# 3_Motor.net
KiCad netlist of a schematic drawn in Altium Designer
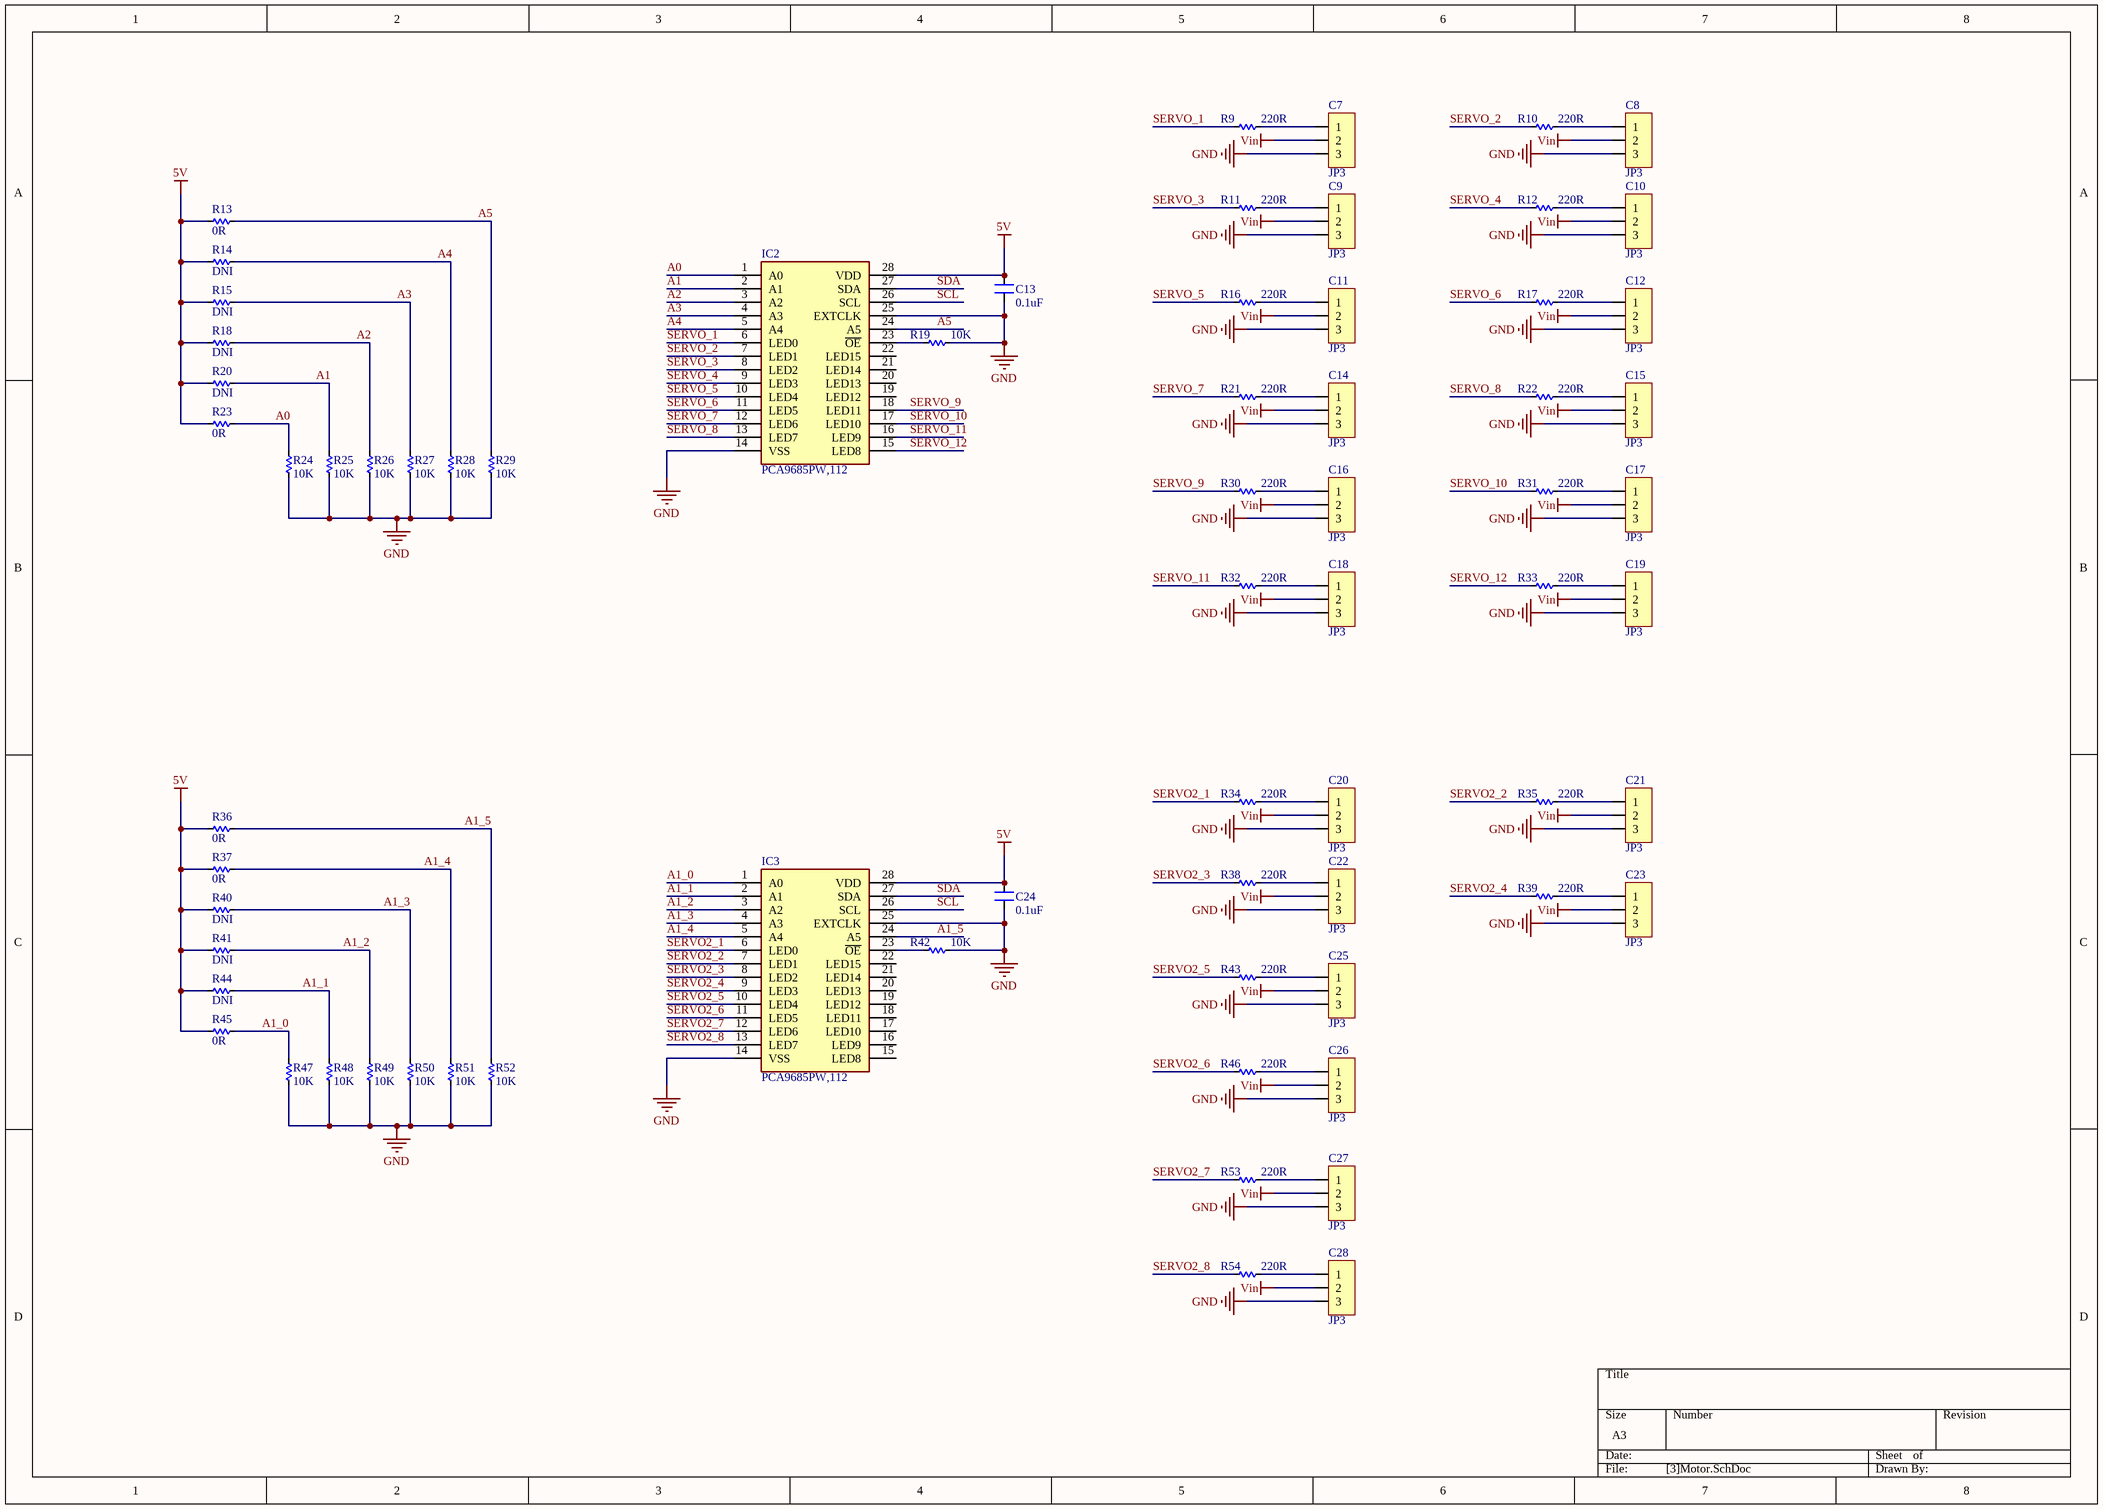
[diagram p0: [3]Motor.SchDoc]

(export (version "E")
  (design (tool "Eeschema 10.0.6"))
  (components
    (comp (ref "C7")
      (value "JP3")
      (footprint "JP3-D1T")
      (description "WR-PHD 2.54 mm Angled Socket Header")
      (fields
        (field (name "MANUFACTURER") "Würth Elektronik eiSos GmbH")
        (field (name "PARTNO") "613003143121")
        (field (name "CREATED BY") "Karrer Zheng")
      )
      (libsource (lib "LIBRARY") (part "JP3"))
    )
    (comp (ref "C8")
      (value "JP3")
      (footprint "JP3-D1T")
      (description "WR-PHD 2.54 mm Angled Socket Header")
      (fields
        (field (name "MANUFACTURER") "Würth Elektronik eiSos GmbH")
        (field (name "PARTNO") "613003143121")
        (field (name "CREATED BY") "Karrer Zheng")
      )
      (libsource (lib "LIBRARY") (part "JP3"))
    )
    (comp (ref "C9")
      (value "JP3")
      (footprint "JP3-D1T")
      (description "WR-PHD 2.54 mm Angled Socket Header")
      (fields
        (field (name "MANUFACTURER") "Würth Elektronik eiSos GmbH")
        (field (name "PARTNO") "613003143121")
        (field (name "CREATED BY") "Karrer Zheng")
      )
      (libsource (lib "LIBRARY") (part "JP3"))
    )
    (comp (ref "C10")
      (value "JP3")
      (footprint "JP3-D1T")
      (description "WR-PHD 2.54 mm Angled Socket Header")
      (fields
        (field (name "MANUFACTURER") "Würth Elektronik eiSos GmbH")
        (field (name "PARTNO") "613003143121")
        (field (name "CREATED BY") "Karrer Zheng")
      )
      (libsource (lib "LIBRARY") (part "JP3"))
    )
    (comp (ref "C11")
      (value "JP3")
      (footprint "JP3-D1T")
      (description "WR-PHD 2.54 mm Angled Socket Header")
      (fields
        (field (name "MANUFACTURER") "Würth Elektronik eiSos GmbH")
        (field (name "PARTNO") "613003143121")
        (field (name "CREATED BY") "Karrer Zheng")
      )
      (libsource (lib "LIBRARY") (part "JP3"))
    )
    (comp (ref "C12")
      (value "JP3")
      (footprint "JP3-D1T")
      (description "WR-PHD 2.54 mm Angled Socket Header")
      (fields
        (field (name "MANUFACTURER") "Würth Elektronik eiSos GmbH")
        (field (name "PARTNO") "613003143121")
        (field (name "CREATED BY") "Karrer Zheng")
      )
      (libsource (lib "LIBRARY") (part "JP3"))
    )
    (comp (ref "C13")
      (value "0.1uF")
      (footprint "CN-SMD-0603")
      (description "Tu gom")
      (libsource (lib "LIBTanCN") (part "CN"))
    )
    (comp (ref "C14")
      (value "JP3")
      (footprint "JP3-D1T")
      (description "WR-PHD 2.54 mm Angled Socket Header")
      (fields
        (field (name "MANUFACTURER") "Würth Elektronik eiSos GmbH")
        (field (name "PARTNO") "613003143121")
        (field (name "CREATED BY") "Karrer Zheng")
      )
      (libsource (lib "LIBRARY") (part "JP3"))
    )
    (comp (ref "C15")
      (value "JP3")
      (footprint "JP3-D1T")
      (description "WR-PHD 2.54 mm Angled Socket Header")
      (fields
        (field (name "MANUFACTURER") "Würth Elektronik eiSos GmbH")
        (field (name "PARTNO") "613003143121")
        (field (name "CREATED BY") "Karrer Zheng")
      )
      (libsource (lib "LIBRARY") (part "JP3"))
    )
    (comp (ref "C16")
      (value "JP3")
      (footprint "JP3-D1T")
      (description "WR-PHD 2.54 mm Angled Socket Header")
      (fields
        (field (name "MANUFACTURER") "Würth Elektronik eiSos GmbH")
        (field (name "PARTNO") "613003143121")
        (field (name "CREATED BY") "Karrer Zheng")
      )
      (libsource (lib "LIBRARY") (part "JP3"))
    )
    (comp (ref "C17")
      (value "JP3")
      (footprint "JP3-D1T")
      (description "WR-PHD 2.54 mm Angled Socket Header")
      (fields
        (field (name "MANUFACTURER") "Würth Elektronik eiSos GmbH")
        (field (name "PARTNO") "613003143121")
        (field (name "CREATED BY") "Karrer Zheng")
      )
      (libsource (lib "LIBRARY") (part "JP3"))
    )
    (comp (ref "C18")
      (value "JP3")
      (footprint "JP3-D1T")
      (description "WR-PHD 2.54 mm Angled Socket Header")
      (fields
        (field (name "MANUFACTURER") "Würth Elektronik eiSos GmbH")
        (field (name "PARTNO") "613003143121")
        (field (name "CREATED BY") "Karrer Zheng")
      )
      (libsource (lib "LIBRARY") (part "JP3"))
    )
    (comp (ref "C19")
      (value "JP3")
      (footprint "JP3-D1T")
      (description "WR-PHD 2.54 mm Angled Socket Header")
      (fields
        (field (name "MANUFACTURER") "Würth Elektronik eiSos GmbH")
        (field (name "PARTNO") "613003143121")
        (field (name "CREATED BY") "Karrer Zheng")
      )
      (libsource (lib "LIBRARY") (part "JP3"))
    )
    (comp (ref "C20")
      (value "JP3")
      (footprint "JP3-D1T")
      (description "WR-PHD 2.54 mm Angled Socket Header")
      (fields
        (field (name "MANUFACTURER") "Würth Elektronik eiSos GmbH")
        (field (name "PARTNO") "613003143121")
        (field (name "CREATED BY") "Karrer Zheng")
      )
      (libsource (lib "LIBRARY") (part "JP3"))
    )
    (comp (ref "C21")
      (value "JP3")
      (footprint "JP3-D1T")
      (description "WR-PHD 2.54 mm Angled Socket Header")
      (fields
        (field (name "MANUFACTURER") "Würth Elektronik eiSos GmbH")
        (field (name "PARTNO") "613003143121")
        (field (name "CREATED BY") "Karrer Zheng")
      )
      (libsource (lib "LIBRARY") (part "JP3"))
    )
    (comp (ref "C22")
      (value "JP3")
      (footprint "JP3-D1T")
      (description "WR-PHD 2.54 mm Angled Socket Header")
      (fields
        (field (name "MANUFACTURER") "Würth Elektronik eiSos GmbH")
        (field (name "PARTNO") "613003143121")
        (field (name "CREATED BY") "Karrer Zheng")
      )
      (libsource (lib "LIBRARY") (part "JP3"))
    )
    (comp (ref "C23")
      (value "JP3")
      (footprint "JP3-D1T")
      (description "WR-PHD 2.54 mm Angled Socket Header")
      (fields
        (field (name "MANUFACTURER") "Würth Elektronik eiSos GmbH")
        (field (name "PARTNO") "613003143121")
        (field (name "CREATED BY") "Karrer Zheng")
      )
      (libsource (lib "LIBRARY") (part "JP3"))
    )
    (comp (ref "C24")
      (value "0.1uF")
      (footprint "CN-SMD-0603")
      (description "Tu gom")
      (libsource (lib "LIBTanCN") (part "CN"))
    )
    (comp (ref "C25")
      (value "JP3")
      (footprint "JP3-D1T")
      (description "WR-PHD 2.54 mm Angled Socket Header")
      (fields
        (field (name "MANUFACTURER") "Würth Elektronik eiSos GmbH")
        (field (name "PARTNO") "613003143121")
        (field (name "CREATED BY") "Karrer Zheng")
      )
      (libsource (lib "LIBRARY") (part "JP3"))
    )
    (comp (ref "C26")
      (value "JP3")
      (footprint "JP3-D1T")
      (description "WR-PHD 2.54 mm Angled Socket Header")
      (fields
        (field (name "MANUFACTURER") "Würth Elektronik eiSos GmbH")
        (field (name "PARTNO") "613003143121")
        (field (name "CREATED BY") "Karrer Zheng")
      )
      (libsource (lib "LIBRARY") (part "JP3"))
    )
    (comp (ref "C27")
      (value "JP3")
      (footprint "JP3-D1T")
      (description "WR-PHD 2.54 mm Angled Socket Header")
      (fields
        (field (name "MANUFACTURER") "Würth Elektronik eiSos GmbH")
        (field (name "PARTNO") "613003143121")
        (field (name "CREATED BY") "Karrer Zheng")
      )
      (libsource (lib "LIBRARY") (part "JP3"))
    )
    (comp (ref "C28")
      (value "JP3")
      (footprint "JP3-D1T")
      (description "WR-PHD 2.54 mm Angled Socket Header")
      (fields
        (field (name "MANUFACTURER") "Würth Elektronik eiSos GmbH")
        (field (name "PARTNO") "613003143121")
        (field (name "CREATED BY") "Karrer Zheng")
      )
      (libsource (lib "LIBRARY") (part "JP3"))
    )
    (comp (ref "IC2")
      (value "PCA9685PW,112")
      (footprint "SamacSys:SOP65P640X110-28N")
      (description "Integrated Circuit")
      (fields (field (name "MOUSER PART NUMBER") "771-PCA9685PW,112"))
      (libsource (lib "*") (part "PCA9685PW,112"))
    )
    (comp (ref "IC3")
      (value "PCA9685PW,112")
      (footprint "SamacSys:SOP65P640X110-28N")
      (description "Integrated Circuit")
      (fields (field (name "MOUSER PART NUMBER") "771-PCA9685PW,112"))
      (libsource (lib "*") (part "PCA9685PW,112"))
    )
    (comp (ref "R9")
      (value "220R")
      (footprint "RES-SMD-0603")
      (description "Resistor")
      (fields
        (field (name "MANUFACTURER") "Generic Components")
        (field (name "PUBLISHER") "Altium Hobart Technology Centre")
      )
      (libsource (lib "LIBRARY") (part "Res-SMD"))
    )
    (comp (ref "R10")
      (value "220R")
      (footprint "RES-SMD-0603")
      (description "Resistor")
      (fields
        (field (name "MANUFACTURER") "Generic Components")
        (field (name "PUBLISHER") "Altium Hobart Technology Centre")
      )
      (libsource (lib "LIBRARY") (part "Res-SMD"))
    )
    (comp (ref "R11")
      (value "220R")
      (footprint "RES-SMD-0603")
      (description "Resistor")
      (fields
        (field (name "MANUFACTURER") "Generic Components")
        (field (name "PUBLISHER") "Altium Hobart Technology Centre")
      )
      (libsource (lib "LIBRARY") (part "Res-SMD"))
    )
    (comp (ref "R12")
      (value "220R")
      (footprint "RES-SMD-0603")
      (description "Resistor")
      (fields
        (field (name "MANUFACTURER") "Generic Components")
        (field (name "PUBLISHER") "Altium Hobart Technology Centre")
      )
      (libsource (lib "LIBRARY") (part "Res-SMD"))
    )
    (comp (ref "R13")
      (value "0R")
      (footprint "RES-SMD-0603")
      (description "Resistor")
      (fields
        (field (name "MANUFACTURER") "Generic Components")
        (field (name "PUBLISHER") "Altium Hobart Technology Centre")
      )
      (libsource (lib "LIBRARY") (part "Res-SMD"))
    )
    (comp (ref "R14")
      (value "DNI")
      (footprint "RES-SMD-0603")
      (description "Resistor")
      (fields
        (field (name "MANUFACTURER") "Generic Components")
        (field (name "PUBLISHER") "Altium Hobart Technology Centre")
      )
      (libsource (lib "LIBRARY") (part "Res-SMD"))
    )
    (comp (ref "R15")
      (value "DNI")
      (footprint "RES-SMD-0603")
      (description "Resistor")
      (fields
        (field (name "MANUFACTURER") "Generic Components")
        (field (name "PUBLISHER") "Altium Hobart Technology Centre")
      )
      (libsource (lib "LIBRARY") (part "Res-SMD"))
    )
    (comp (ref "R16")
      (value "220R")
      (footprint "RES-SMD-0603")
      (description "Resistor")
      (fields
        (field (name "MANUFACTURER") "Generic Components")
        (field (name "PUBLISHER") "Altium Hobart Technology Centre")
      )
      (libsource (lib "LIBRARY") (part "Res-SMD"))
    )
    (comp (ref "R17")
      (value "220R")
      (footprint "RES-SMD-0603")
      (description "Resistor")
      (fields
        (field (name "MANUFACTURER") "Generic Components")
        (field (name "PUBLISHER") "Altium Hobart Technology Centre")
      )
      (libsource (lib "LIBRARY") (part "Res-SMD"))
    )
    (comp (ref "R18")
      (value "DNI")
      (footprint "RES-SMD-0603")
      (description "Resistor")
      (fields
        (field (name "MANUFACTURER") "Generic Components")
        (field (name "PUBLISHER") "Altium Hobart Technology Centre")
      )
      (libsource (lib "LIBRARY") (part "Res-SMD"))
    )
    (comp (ref "R19")
      (value "10K")
      (footprint "RES-SMD-0603")
      (description "Resistor")
      (fields
        (field (name "MANUFACTURER") "Generic Components")
        (field (name "PUBLISHER") "Altium Hobart Technology Centre")
      )
      (libsource (lib "LIBRARY") (part "Res-SMD"))
    )
    (comp (ref "R20")
      (value "DNI")
      (footprint "RES-SMD-0603")
      (description "Resistor")
      (fields
        (field (name "MANUFACTURER") "Generic Components")
        (field (name "PUBLISHER") "Altium Hobart Technology Centre")
      )
      (libsource (lib "LIBRARY") (part "Res-SMD"))
    )
    (comp (ref "R21")
      (value "220R")
      (footprint "RES-SMD-0603")
      (description "Resistor")
      (fields
        (field (name "MANUFACTURER") "Generic Components")
        (field (name "PUBLISHER") "Altium Hobart Technology Centre")
      )
      (libsource (lib "LIBRARY") (part "Res-SMD"))
    )
    (comp (ref "R22")
      (value "220R")
      (footprint "RES-SMD-0603")
      (description "Resistor")
      (fields
        (field (name "MANUFACTURER") "Generic Components")
        (field (name "PUBLISHER") "Altium Hobart Technology Centre")
      )
      (libsource (lib "LIBRARY") (part "Res-SMD"))
    )
    (comp (ref "R23")
      (value "0R")
      (footprint "RES-SMD-0603")
      (description "Resistor")
      (fields
        (field (name "MANUFACTURER") "Generic Components")
        (field (name "PUBLISHER") "Altium Hobart Technology Centre")
      )
      (libsource (lib "LIBRARY") (part "Res-SMD"))
    )
    (comp (ref "R24")
      (value "10K")
      (footprint "RES-SMD-0603")
      (description "Resistor")
      (fields
        (field (name "MANUFACTURER") "Generic Components")
        (field (name "PUBLISHER") "Altium Hobart Technology Centre")
      )
      (libsource (lib "LIBRARY") (part "Res-SMD"))
    )
    (comp (ref "R25")
      (value "10K")
      (footprint "RES-SMD-0603")
      (description "Resistor")
      (fields
        (field (name "MANUFACTURER") "Generic Components")
        (field (name "PUBLISHER") "Altium Hobart Technology Centre")
      )
      (libsource (lib "LIBRARY") (part "Res-SMD"))
    )
    (comp (ref "R26")
      (value "10K")
      (footprint "RES-SMD-0603")
      (description "Resistor")
      (fields
        (field (name "MANUFACTURER") "Generic Components")
        (field (name "PUBLISHER") "Altium Hobart Technology Centre")
      )
      (libsource (lib "LIBRARY") (part "Res-SMD"))
    )
    (comp (ref "R27")
      (value "10K")
      (footprint "RES-SMD-0603")
      (description "Resistor")
      (fields
        (field (name "MANUFACTURER") "Generic Components")
        (field (name "PUBLISHER") "Altium Hobart Technology Centre")
      )
      (libsource (lib "LIBRARY") (part "Res-SMD"))
    )
    (comp (ref "R28")
      (value "10K")
      (footprint "RES-SMD-0603")
      (description "Resistor")
      (fields
        (field (name "MANUFACTURER") "Generic Components")
        (field (name "PUBLISHER") "Altium Hobart Technology Centre")
      )
      (libsource (lib "LIBRARY") (part "Res-SMD"))
    )
    (comp (ref "R29")
      (value "10K")
      (footprint "RES-SMD-0603")
      (description "Resistor")
      (fields
        (field (name "MANUFACTURER") "Generic Components")
        (field (name "PUBLISHER") "Altium Hobart Technology Centre")
      )
      (libsource (lib "LIBRARY") (part "Res-SMD"))
    )
    (comp (ref "R30")
      (value "220R")
      (footprint "RES-SMD-0603")
      (description "Resistor")
      (fields
        (field (name "MANUFACTURER") "Generic Components")
        (field (name "PUBLISHER") "Altium Hobart Technology Centre")
      )
      (libsource (lib "LIBRARY") (part "Res-SMD"))
    )
    (comp (ref "R31")
      (value "220R")
      (footprint "RES-SMD-0603")
      (description "Resistor")
      (fields
        (field (name "MANUFACTURER") "Generic Components")
        (field (name "PUBLISHER") "Altium Hobart Technology Centre")
      )
      (libsource (lib "LIBRARY") (part "Res-SMD"))
    )
    (comp (ref "R32")
      (value "220R")
      (footprint "RES-SMD-0603")
      (description "Resistor")
      (fields
        (field (name "MANUFACTURER") "Generic Components")
        (field (name "PUBLISHER") "Altium Hobart Technology Centre")
      )
      (libsource (lib "LIBRARY") (part "Res-SMD"))
    )
    (comp (ref "R33")
      (value "220R")
      (footprint "RES-SMD-0603")
      (description "Resistor")
      (fields
        (field (name "MANUFACTURER") "Generic Components")
        (field (name "PUBLISHER") "Altium Hobart Technology Centre")
      )
      (libsource (lib "LIBRARY") (part "Res-SMD"))
    )
    (comp (ref "R34")
      (value "220R")
      (footprint "RES-SMD-0603")
      (description "Resistor")
      (fields
        (field (name "MANUFACTURER") "Generic Components")
        (field (name "PUBLISHER") "Altium Hobart Technology Centre")
      )
      (libsource (lib "LIBRARY") (part "Res-SMD"))
    )
    (comp (ref "R35")
      (value "220R")
      (footprint "RES-SMD-0603")
      (description "Resistor")
      (fields
        (field (name "MANUFACTURER") "Generic Components")
        (field (name "PUBLISHER") "Altium Hobart Technology Centre")
      )
      (libsource (lib "LIBRARY") (part "Res-SMD"))
    )
    (comp (ref "R36")
      (value "0R")
      (footprint "RES-SMD-0603")
      (description "Resistor")
      (fields
        (field (name "MANUFACTURER") "Generic Components")
        (field (name "PUBLISHER") "Altium Hobart Technology Centre")
      )
      (libsource (lib "LIBRARY") (part "Res-SMD"))
    )
    (comp (ref "R37")
      (value "0R")
      (footprint "RES-SMD-0603")
      (description "Resistor")
      (fields
        (field (name "MANUFACTURER") "Generic Components")
        (field (name "PUBLISHER") "Altium Hobart Technology Centre")
      )
      (libsource (lib "LIBRARY") (part "Res-SMD"))
    )
    (comp (ref "R38")
      (value "220R")
      (footprint "RES-SMD-0603")
      (description "Resistor")
      (fields
        (field (name "MANUFACTURER") "Generic Components")
        (field (name "PUBLISHER") "Altium Hobart Technology Centre")
      )
      (libsource (lib "LIBRARY") (part "Res-SMD"))
    )
    (comp (ref "R39")
      (value "220R")
      (footprint "RES-SMD-0603")
      (description "Resistor")
      (fields
        (field (name "MANUFACTURER") "Generic Components")
        (field (name "PUBLISHER") "Altium Hobart Technology Centre")
      )
      (libsource (lib "LIBRARY") (part "Res-SMD"))
    )
    (comp (ref "R40")
      (value "DNI")
      (footprint "RES-SMD-0603")
      (description "Resistor")
      (fields
        (field (name "MANUFACTURER") "Generic Components")
        (field (name "PUBLISHER") "Altium Hobart Technology Centre")
      )
      (libsource (lib "LIBRARY") (part "Res-SMD"))
    )
    (comp (ref "R41")
      (value "DNI")
      (footprint "RES-SMD-0603")
      (description "Resistor")
      (fields
        (field (name "MANUFACTURER") "Generic Components")
        (field (name "PUBLISHER") "Altium Hobart Technology Centre")
      )
      (libsource (lib "LIBRARY") (part "Res-SMD"))
    )
    (comp (ref "R42")
      (value "10K")
      (footprint "RES-SMD-0603")
      (description "Resistor")
      (fields
        (field (name "MANUFACTURER") "Generic Components")
        (field (name "PUBLISHER") "Altium Hobart Technology Centre")
      )
      (libsource (lib "LIBRARY") (part "Res-SMD"))
    )
    (comp (ref "R43")
      (value "220R")
      (footprint "RES-SMD-0603")
      (description "Resistor")
      (fields
        (field (name "MANUFACTURER") "Generic Components")
        (field (name "PUBLISHER") "Altium Hobart Technology Centre")
      )
      (libsource (lib "LIBRARY") (part "Res-SMD"))
    )
    (comp (ref "R44")
      (value "DNI")
      (footprint "RES-SMD-0603")
      (description "Resistor")
      (fields
        (field (name "MANUFACTURER") "Generic Components")
        (field (name "PUBLISHER") "Altium Hobart Technology Centre")
      )
      (libsource (lib "LIBRARY") (part "Res-SMD"))
    )
    (comp (ref "R45")
      (value "0R")
      (footprint "RES-SMD-0603")
      (description "Resistor")
      (fields
        (field (name "MANUFACTURER") "Generic Components")
        (field (name "PUBLISHER") "Altium Hobart Technology Centre")
      )
      (libsource (lib "LIBRARY") (part "Res-SMD"))
    )
    (comp (ref "R46")
      (value "220R")
      (footprint "RES-SMD-0603")
      (description "Resistor")
      (fields
        (field (name "MANUFACTURER") "Generic Components")
        (field (name "PUBLISHER") "Altium Hobart Technology Centre")
      )
      (libsource (lib "LIBRARY") (part "Res-SMD"))
    )
    (comp (ref "R47")
      (value "10K")
      (footprint "RES-SMD-0603")
      (description "Resistor")
      (fields
        (field (name "MANUFACTURER") "Generic Components")
        (field (name "PUBLISHER") "Altium Hobart Technology Centre")
      )
      (libsource (lib "LIBRARY") (part "Res-SMD"))
    )
    (comp (ref "R48")
      (value "10K")
      (footprint "RES-SMD-0603")
      (description "Resistor")
      (fields
        (field (name "MANUFACTURER") "Generic Components")
        (field (name "PUBLISHER") "Altium Hobart Technology Centre")
      )
      (libsource (lib "LIBRARY") (part "Res-SMD"))
    )
    (comp (ref "R49")
      (value "10K")
      (footprint "RES-SMD-0603")
      (description "Resistor")
      (fields
        (field (name "MANUFACTURER") "Generic Components")
        (field (name "PUBLISHER") "Altium Hobart Technology Centre")
      )
      (libsource (lib "LIBRARY") (part "Res-SMD"))
    )
    (comp (ref "R50")
      (value "10K")
      (footprint "RES-SMD-0603")
      (description "Resistor")
      (fields
        (field (name "MANUFACTURER") "Generic Components")
        (field (name "PUBLISHER") "Altium Hobart Technology Centre")
      )
      (libsource (lib "LIBRARY") (part "Res-SMD"))
    )
    (comp (ref "R51")
      (value "10K")
      (footprint "RES-SMD-0603")
      (description "Resistor")
      (fields
        (field (name "MANUFACTURER") "Generic Components")
        (field (name "PUBLISHER") "Altium Hobart Technology Centre")
      )
      (libsource (lib "LIBRARY") (part "Res-SMD"))
    )
    (comp (ref "R52")
      (value "10K")
      (footprint "RES-SMD-0603")
      (description "Resistor")
      (fields
        (field (name "MANUFACTURER") "Generic Components")
        (field (name "PUBLISHER") "Altium Hobart Technology Centre")
      )
      (libsource (lib "LIBRARY") (part "Res-SMD"))
    )
    (comp (ref "R53")
      (value "220R")
      (footprint "RES-SMD-0603")
      (description "Resistor")
      (fields
        (field (name "MANUFACTURER") "Generic Components")
        (field (name "PUBLISHER") "Altium Hobart Technology Centre")
      )
      (libsource (lib "LIBRARY") (part "Res-SMD"))
    )
    (comp (ref "R54")
      (value "220R")
      (footprint "RES-SMD-0603")
      (description "Resistor")
      (fields
        (field (name "MANUFACTURER") "Generic Components")
        (field (name "PUBLISHER") "Altium Hobart Technology Centre")
      )
      (libsource (lib "LIBRARY") (part "Res-SMD"))
    )
  )
  (nets
    (net (code "1") (name "/A0") (class "Default")
      (node (ref "IC2") (pin "1") (pinfunction "A0_1") (pintype "passive"))
      (node (ref "R23") (pin "1") (pinfunction "1_1") (pintype "passive"))
      (node (ref "R24") (pin "1") (pinfunction "1_1") (pintype "passive"))
    )
    (net (code "2") (name "/A1") (class "Default")
      (node (ref "IC2") (pin "2") (pinfunction "A1_2") (pintype "passive"))
      (node (ref "R20") (pin "1") (pinfunction "1_1") (pintype "passive"))
      (node (ref "R25") (pin "1") (pinfunction "1_1") (pintype "passive"))
    )
    (net (code "3") (name "/A1_0") (class "Default")
      (node (ref "IC3") (pin "1") (pinfunction "A0_1") (pintype "passive"))
      (node (ref "R45") (pin "1") (pinfunction "1_1") (pintype "passive"))
      (node (ref "R47") (pin "1") (pinfunction "1_1") (pintype "passive"))
    )
    (net (code "4") (name "/A1_1") (class "Default")
      (node (ref "IC3") (pin "2") (pinfunction "A1_2") (pintype "passive"))
      (node (ref "R44") (pin "1") (pinfunction "1_1") (pintype "passive"))
      (node (ref "R48") (pin "1") (pinfunction "1_1") (pintype "passive"))
    )
    (net (code "5") (name "/A1_2") (class "Default")
      (node (ref "IC3") (pin "3") (pinfunction "A2_3") (pintype "passive"))
      (node (ref "R41") (pin "1") (pinfunction "1_1") (pintype "passive"))
      (node (ref "R49") (pin "1") (pinfunction "1_1") (pintype "passive"))
    )
    (net (code "6") (name "/A1_3") (class "Default")
      (node (ref "IC3") (pin "4") (pinfunction "A3_4") (pintype "passive"))
      (node (ref "R40") (pin "1") (pinfunction "1_1") (pintype "passive"))
      (node (ref "R50") (pin "1") (pinfunction "1_1") (pintype "passive"))
    )
    (net (code "7") (name "/A1_4") (class "Default")
      (node (ref "IC3") (pin "5") (pinfunction "A4_5") (pintype "passive"))
      (node (ref "R37") (pin "1") (pinfunction "1_1") (pintype "passive"))
      (node (ref "R51") (pin "1") (pinfunction "1_1") (pintype "passive"))
    )
    (net (code "8") (name "/A1_5") (class "Default")
      (node (ref "IC3") (pin "24") (pinfunction "A5_24") (pintype "passive"))
      (node (ref "R36") (pin "1") (pinfunction "1_1") (pintype "passive"))
      (node (ref "R52") (pin "1") (pinfunction "1_1") (pintype "passive"))
    )
    (net (code "9") (name "/A2") (class "Default")
      (node (ref "IC2") (pin "3") (pinfunction "A2_3") (pintype "passive"))
      (node (ref "R18") (pin "1") (pinfunction "1_1") (pintype "passive"))
      (node (ref "R26") (pin "1") (pinfunction "1_1") (pintype "passive"))
    )
    (net (code "10") (name "/A3") (class "Default")
      (node (ref "IC2") (pin "4") (pinfunction "A3_4") (pintype "passive"))
      (node (ref "R15") (pin "1") (pinfunction "1_1") (pintype "passive"))
      (node (ref "R27") (pin "1") (pinfunction "1_1") (pintype "passive"))
    )
    (net (code "11") (name "/A4") (class "Default")
      (node (ref "IC2") (pin "5") (pinfunction "A4_5") (pintype "passive"))
      (node (ref "R14") (pin "1") (pinfunction "1_1") (pintype "passive"))
      (node (ref "R28") (pin "1") (pinfunction "1_1") (pintype "passive"))
    )
    (net (code "12") (name "/A5") (class "Default")
      (node (ref "IC2") (pin "24") (pinfunction "A5_24") (pintype "passive"))
      (node (ref "R13") (pin "1") (pinfunction "1_1") (pintype "passive"))
      (node (ref "R29") (pin "1") (pinfunction "1_1") (pintype "passive"))
    )
    (net (code "13") (name "/SCL") (class "Default")
      (node (ref "IC2") (pin "26") (pinfunction "SCL_26") (pintype "passive"))
      (node (ref "IC3") (pin "26") (pinfunction "SCL_26") (pintype "passive"))
    )
    (net (code "14") (name "/SDA") (class "Default")
      (node (ref "IC2") (pin "27") (pinfunction "SDA_27") (pintype "passive"))
      (node (ref "IC3") (pin "27") (pinfunction "SDA_27") (pintype "passive"))
    )
    (net (code "15") (name "/SERVO2_1") (class "Default")
      (node (ref "IC3") (pin "6") (pinfunction "LED0_6") (pintype "passive"))
      (node (ref "R34") (pin "1") (pinfunction "1_1") (pintype "passive"))
    )
    (net (code "16") (name "/SERVO2_2") (class "Default")
      (node (ref "IC3") (pin "7") (pinfunction "LED1_7") (pintype "passive"))
      (node (ref "R35") (pin "1") (pinfunction "1_1") (pintype "passive"))
    )
    (net (code "17") (name "/SERVO2_3") (class "Default")
      (node (ref "IC3") (pin "8") (pinfunction "LED2_8") (pintype "passive"))
      (node (ref "R38") (pin "1") (pinfunction "1_1") (pintype "passive"))
    )
    (net (code "18") (name "/SERVO2_4") (class "Default")
      (node (ref "IC3") (pin "9") (pinfunction "LED3_9") (pintype "passive"))
      (node (ref "R39") (pin "1") (pinfunction "1_1") (pintype "passive"))
    )
    (net (code "19") (name "/SERVO2_5") (class "Default")
      (node (ref "IC3") (pin "10") (pinfunction "LED4_10") (pintype "passive"))
      (node (ref "R43") (pin "1") (pinfunction "1_1") (pintype "passive"))
    )
    (net (code "20") (name "/SERVO2_6") (class "Default")
      (node (ref "IC3") (pin "11") (pinfunction "LED5_11") (pintype "passive"))
      (node (ref "R46") (pin "1") (pinfunction "1_1") (pintype "passive"))
    )
    (net (code "21") (name "/SERVO2_7") (class "Default")
      (node (ref "IC3") (pin "12") (pinfunction "LED6_12") (pintype "passive"))
      (node (ref "R53") (pin "1") (pinfunction "1_1") (pintype "passive"))
    )
    (net (code "22") (name "/SERVO2_8") (class "Default")
      (node (ref "IC3") (pin "13") (pinfunction "LED7_13") (pintype "passive"))
      (node (ref "R54") (pin "1") (pinfunction "1_1") (pintype "passive"))
    )
    (net (code "23") (name "/SERVO_1") (class "Default")
      (node (ref "IC2") (pin "6") (pinfunction "LED0_6") (pintype "passive"))
      (node (ref "R9") (pin "1") (pinfunction "1_1") (pintype "passive"))
    )
    (net (code "24") (name "/SERVO_2") (class "Default")
      (node (ref "IC2") (pin "7") (pinfunction "LED1_7") (pintype "passive"))
      (node (ref "R10") (pin "1") (pinfunction "1_1") (pintype "passive"))
    )
    (net (code "25") (name "/SERVO_3") (class "Default")
      (node (ref "IC2") (pin "8") (pinfunction "LED2_8") (pintype "passive"))
      (node (ref "R11") (pin "1") (pinfunction "1_1") (pintype "passive"))
    )
    (net (code "26") (name "/SERVO_4") (class "Default")
      (node (ref "IC2") (pin "9") (pinfunction "LED3_9") (pintype "passive"))
      (node (ref "R12") (pin "1") (pinfunction "1_1") (pintype "passive"))
    )
    (net (code "27") (name "/SERVO_5") (class "Default")
      (node (ref "IC2") (pin "10") (pinfunction "LED4_10") (pintype "passive"))
      (node (ref "R16") (pin "1") (pinfunction "1_1") (pintype "passive"))
    )
    (net (code "28") (name "/SERVO_6") (class "Default")
      (node (ref "IC2") (pin "11") (pinfunction "LED5_11") (pintype "passive"))
      (node (ref "R17") (pin "1") (pinfunction "1_1") (pintype "passive"))
    )
    (net (code "29") (name "/SERVO_7") (class "Default")
      (node (ref "IC2") (pin "12") (pinfunction "LED6_12") (pintype "passive"))
      (node (ref "R21") (pin "1") (pinfunction "1_1") (pintype "passive"))
    )
    (net (code "30") (name "/SERVO_8") (class "Default")
      (node (ref "IC2") (pin "13") (pinfunction "LED7_13") (pintype "passive"))
      (node (ref "R22") (pin "1") (pinfunction "1_1") (pintype "passive"))
    )
    (net (code "31") (name "/SERVO_9") (class "Default")
      (node (ref "IC2") (pin "18") (pinfunction "LED11_18") (pintype "passive"))
      (node (ref "R30") (pin "1") (pinfunction "1_1") (pintype "passive"))
    )
    (net (code "32") (name "/SERVO_10") (class "Default")
      (node (ref "IC2") (pin "17") (pinfunction "LED10_17") (pintype "passive"))
      (node (ref "R31") (pin "1") (pinfunction "1_1") (pintype "passive"))
    )
    (net (code "33") (name "/SERVO_11") (class "Default")
      (node (ref "IC2") (pin "16") (pinfunction "LED9_16") (pintype "passive"))
      (node (ref "R32") (pin "1") (pinfunction "1_1") (pintype "passive"))
    )
    (net (code "34") (name "/SERVO_12") (class "Default")
      (node (ref "IC2") (pin "15") (pinfunction "LED8_15") (pintype "passive"))
      (node (ref "R33") (pin "1") (pinfunction "1_1") (pintype "passive"))
    )
    (net (code "35") (name "5V") (class "Default")
      (node (ref "C13") (pin "2") (pinfunction "2_2") (pintype "passive"))
      (node (ref "C24") (pin "2") (pinfunction "2_2") (pintype "passive"))
      (node (ref "IC2") (pin "28") (pinfunction "VDD_28") (pintype "passive"))
      (node (ref "IC3") (pin "28") (pinfunction "VDD_28") (pintype "passive"))
      (node (ref "R13") (pin "2") (pinfunction "2_2") (pintype "passive"))
      (node (ref "R14") (pin "2") (pinfunction "2_2") (pintype "passive"))
      (node (ref "R15") (pin "2") (pinfunction "2_2") (pintype "passive"))
      (node (ref "R18") (pin "2") (pinfunction "2_2") (pintype "passive"))
      (node (ref "R20") (pin "2") (pinfunction "2_2") (pintype "passive"))
      (node (ref "R23") (pin "2") (pinfunction "2_2") (pintype "passive"))
      (node (ref "R36") (pin "2") (pinfunction "2_2") (pintype "passive"))
      (node (ref "R37") (pin "2") (pinfunction "2_2") (pintype "passive"))
      (node (ref "R40") (pin "2") (pinfunction "2_2") (pintype "passive"))
      (node (ref "R41") (pin "2") (pinfunction "2_2") (pintype "passive"))
      (node (ref "R44") (pin "2") (pinfunction "2_2") (pintype "passive"))
      (node (ref "R45") (pin "2") (pinfunction "2_2") (pintype "passive"))
    )
    (net (code "36") (name "GND") (class "Default")
      (node (ref "C10") (pin "3") (pinfunction "3_3") (pintype "passive"))
      (node (ref "C11") (pin "3") (pinfunction "3_3") (pintype "passive"))
      (node (ref "C12") (pin "3") (pinfunction "3_3") (pintype "passive"))
      (node (ref "C13") (pin "1") (pinfunction "1_1") (pintype "passive"))
      (node (ref "C14") (pin "3") (pinfunction "3_3") (pintype "passive"))
      (node (ref "C15") (pin "3") (pinfunction "3_3") (pintype "passive"))
      (node (ref "C16") (pin "3") (pinfunction "3_3") (pintype "passive"))
      (node (ref "C17") (pin "3") (pinfunction "3_3") (pintype "passive"))
      (node (ref "C18") (pin "3") (pinfunction "3_3") (pintype "passive"))
      (node (ref "C19") (pin "3") (pinfunction "3_3") (pintype "passive"))
      (node (ref "C20") (pin "3") (pinfunction "3_3") (pintype "passive"))
      (node (ref "C21") (pin "3") (pinfunction "3_3") (pintype "passive"))
      (node (ref "C22") (pin "3") (pinfunction "3_3") (pintype "passive"))
      (node (ref "C23") (pin "3") (pinfunction "3_3") (pintype "passive"))
      (node (ref "C24") (pin "1") (pinfunction "1_1") (pintype "passive"))
      (node (ref "C25") (pin "3") (pinfunction "3_3") (pintype "passive"))
      (node (ref "C26") (pin "3") (pinfunction "3_3") (pintype "passive"))
      (node (ref "C27") (pin "3") (pinfunction "3_3") (pintype "passive"))
      (node (ref "C28") (pin "3") (pinfunction "3_3") (pintype "passive"))
      (node (ref "C7") (pin "3") (pinfunction "3_3") (pintype "passive"))
      (node (ref "C8") (pin "3") (pinfunction "3_3") (pintype "passive"))
      (node (ref "C9") (pin "3") (pinfunction "3_3") (pintype "passive"))
      (node (ref "IC2") (pin "14") (pinfunction "VSS_14") (pintype "passive"))
      (node (ref "IC2") (pin "25") (pinfunction "EXTCLK_25") (pintype "passive"))
      (node (ref "IC3") (pin "14") (pinfunction "VSS_14") (pintype "passive"))
      (node (ref "IC3") (pin "25") (pinfunction "EXTCLK_25") (pintype "passive"))
      (node (ref "R19") (pin "2") (pinfunction "2_2") (pintype "passive"))
      (node (ref "R24") (pin "2") (pinfunction "2_2") (pintype "passive"))
      (node (ref "R25") (pin "2") (pinfunction "2_2") (pintype "passive"))
      (node (ref "R26") (pin "2") (pinfunction "2_2") (pintype "passive"))
      (node (ref "R27") (pin "2") (pinfunction "2_2") (pintype "passive"))
      (node (ref "R28") (pin "2") (pinfunction "2_2") (pintype "passive"))
      (node (ref "R29") (pin "2") (pinfunction "2_2") (pintype "passive"))
      (node (ref "R42") (pin "2") (pinfunction "2_2") (pintype "passive"))
      (node (ref "R47") (pin "2") (pinfunction "2_2") (pintype "passive"))
      (node (ref "R48") (pin "2") (pinfunction "2_2") (pintype "passive"))
      (node (ref "R49") (pin "2") (pinfunction "2_2") (pintype "passive"))
      (node (ref "R50") (pin "2") (pinfunction "2_2") (pintype "passive"))
      (node (ref "R51") (pin "2") (pinfunction "2_2") (pintype "passive"))
      (node (ref "R52") (pin "2") (pinfunction "2_2") (pintype "passive"))
    )
    (net (code "37") (name "Net-(C7-Pad1)") (class "Default")
      (node (ref "C7") (pin "1") (pinfunction "1_1") (pintype "passive"))
      (node (ref "R9") (pin "2") (pinfunction "2_2") (pintype "passive"))
    )
    (net (code "38") (name "Net-(C8-Pad1)") (class "Default")
      (node (ref "C8") (pin "1") (pinfunction "1_1") (pintype "passive"))
      (node (ref "R10") (pin "2") (pinfunction "2_2") (pintype "passive"))
    )
    (net (code "39") (name "Net-(C9-Pad1)") (class "Default")
      (node (ref "C9") (pin "1") (pinfunction "1_1") (pintype "passive"))
      (node (ref "R11") (pin "2") (pinfunction "2_2") (pintype "passive"))
    )
    (net (code "40") (name "Net-(C10-Pad1)") (class "Default")
      (node (ref "C10") (pin "1") (pinfunction "1_1") (pintype "passive"))
      (node (ref "R12") (pin "2") (pinfunction "2_2") (pintype "passive"))
    )
    (net (code "41") (name "Net-(C11-Pad1)") (class "Default")
      (node (ref "C11") (pin "1") (pinfunction "1_1") (pintype "passive"))
      (node (ref "R16") (pin "2") (pinfunction "2_2") (pintype "passive"))
    )
    (net (code "42") (name "Net-(C12-Pad1)") (class "Default")
      (node (ref "C12") (pin "1") (pinfunction "1_1") (pintype "passive"))
      (node (ref "R17") (pin "2") (pinfunction "2_2") (pintype "passive"))
    )
    (net (code "43") (name "Net-(C14-Pad1)") (class "Default")
      (node (ref "C14") (pin "1") (pinfunction "1_1") (pintype "passive"))
      (node (ref "R21") (pin "2") (pinfunction "2_2") (pintype "passive"))
    )
    (net (code "44") (name "Net-(C15-Pad1)") (class "Default")
      (node (ref "C15") (pin "1") (pinfunction "1_1") (pintype "passive"))
      (node (ref "R22") (pin "2") (pinfunction "2_2") (pintype "passive"))
    )
    (net (code "45") (name "Net-(C16-Pad1)") (class "Default")
      (node (ref "C16") (pin "1") (pinfunction "1_1") (pintype "passive"))
      (node (ref "R30") (pin "2") (pinfunction "2_2") (pintype "passive"))
    )
    (net (code "46") (name "Net-(C17-Pad1)") (class "Default")
      (node (ref "C17") (pin "1") (pinfunction "1_1") (pintype "passive"))
      (node (ref "R31") (pin "2") (pinfunction "2_2") (pintype "passive"))
    )
    (net (code "47") (name "Net-(C18-Pad1)") (class "Default")
      (node (ref "C18") (pin "1") (pinfunction "1_1") (pintype "passive"))
      (node (ref "R32") (pin "2") (pinfunction "2_2") (pintype "passive"))
    )
    (net (code "48") (name "Net-(C19-Pad1)") (class "Default")
      (node (ref "C19") (pin "1") (pinfunction "1_1") (pintype "passive"))
      (node (ref "R33") (pin "2") (pinfunction "2_2") (pintype "passive"))
    )
    (net (code "49") (name "Net-(C20-Pad1)") (class "Default")
      (node (ref "C20") (pin "1") (pinfunction "1_1") (pintype "passive"))
      (node (ref "R34") (pin "2") (pinfunction "2_2") (pintype "passive"))
    )
    (net (code "50") (name "Net-(C21-Pad1)") (class "Default")
      (node (ref "C21") (pin "1") (pinfunction "1_1") (pintype "passive"))
      (node (ref "R35") (pin "2") (pinfunction "2_2") (pintype "passive"))
    )
    (net (code "51") (name "Net-(C22-Pad1)") (class "Default")
      (node (ref "C22") (pin "1") (pinfunction "1_1") (pintype "passive"))
      (node (ref "R38") (pin "2") (pinfunction "2_2") (pintype "passive"))
    )
    (net (code "52") (name "Net-(C23-Pad1)") (class "Default")
      (node (ref "C23") (pin "1") (pinfunction "1_1") (pintype "passive"))
      (node (ref "R39") (pin "2") (pinfunction "2_2") (pintype "passive"))
    )
    (net (code "53") (name "Net-(C25-Pad1)") (class "Default")
      (node (ref "C25") (pin "1") (pinfunction "1_1") (pintype "passive"))
      (node (ref "R43") (pin "2") (pinfunction "2_2") (pintype "passive"))
    )
    (net (code "54") (name "Net-(C26-Pad1)") (class "Default")
      (node (ref "C26") (pin "1") (pinfunction "1_1") (pintype "passive"))
      (node (ref "R46") (pin "2") (pinfunction "2_2") (pintype "passive"))
    )
    (net (code "55") (name "Net-(C27-Pad1)") (class "Default")
      (node (ref "C27") (pin "1") (pinfunction "1_1") (pintype "passive"))
      (node (ref "R53") (pin "2") (pinfunction "2_2") (pintype "passive"))
    )
    (net (code "56") (name "Net-(C28-Pad1)") (class "Default")
      (node (ref "C28") (pin "1") (pinfunction "1_1") (pintype "passive"))
      (node (ref "R54") (pin "2") (pinfunction "2_2") (pintype "passive"))
    )
    (net (code "57") (name "Net-(IC2-~{OE})") (class "Default")
      (node (ref "IC2") (pin "23") (pinfunction "~{OE}_23") (pintype "passive"))
      (node (ref "R19") (pin "1") (pinfunction "1_1") (pintype "passive"))
    )
    (net (code "58") (name "Net-(IC3-~{OE})") (class "Default")
      (node (ref "IC3") (pin "23") (pinfunction "~{OE}_23") (pintype "passive"))
      (node (ref "R42") (pin "1") (pinfunction "1_1") (pintype "passive"))
    )
    (net (code "59") (name "Vin") (class "Default")
      (node (ref "C10") (pin "2") (pinfunction "2_2") (pintype "passive"))
      (node (ref "C11") (pin "2") (pinfunction "2_2") (pintype "passive"))
      (node (ref "C12") (pin "2") (pinfunction "2_2") (pintype "passive"))
      (node (ref "C14") (pin "2") (pinfunction "2_2") (pintype "passive"))
      (node (ref "C15") (pin "2") (pinfunction "2_2") (pintype "passive"))
      (node (ref "C16") (pin "2") (pinfunction "2_2") (pintype "passive"))
      (node (ref "C17") (pin "2") (pinfunction "2_2") (pintype "passive"))
      (node (ref "C18") (pin "2") (pinfunction "2_2") (pintype "passive"))
      (node (ref "C19") (pin "2") (pinfunction "2_2") (pintype "passive"))
      (node (ref "C20") (pin "2") (pinfunction "2_2") (pintype "passive"))
      (node (ref "C21") (pin "2") (pinfunction "2_2") (pintype "passive"))
      (node (ref "C22") (pin "2") (pinfunction "2_2") (pintype "passive"))
      (node (ref "C23") (pin "2") (pinfunction "2_2") (pintype "passive"))
      (node (ref "C25") (pin "2") (pinfunction "2_2") (pintype "passive"))
      (node (ref "C26") (pin "2") (pinfunction "2_2") (pintype "passive"))
      (node (ref "C27") (pin "2") (pinfunction "2_2") (pintype "passive"))
      (node (ref "C28") (pin "2") (pinfunction "2_2") (pintype "passive"))
      (node (ref "C7") (pin "2") (pinfunction "2_2") (pintype "passive"))
      (node (ref "C8") (pin "2") (pinfunction "2_2") (pintype "passive"))
      (node (ref "C9") (pin "2") (pinfunction "2_2") (pintype "passive"))
    )
    (net (code "60") (name "unconnected-(IC2-LED12-Pad19)") (class "Default")
      (node (ref "IC2") (pin "19") (pinfunction "LED12_19") (pintype "passive"))
    )
    (net (code "61") (name "unconnected-(IC2-LED13-Pad20)") (class "Default")
      (node (ref "IC2") (pin "20") (pinfunction "LED13_20") (pintype "passive"))
    )
    (net (code "62") (name "unconnected-(IC2-LED14-Pad21)") (class "Default")
      (node (ref "IC2") (pin "21") (pinfunction "LED14_21") (pintype "passive"))
    )
    (net (code "63") (name "unconnected-(IC2-LED15-Pad22)") (class "Default")
      (node (ref "IC2") (pin "22") (pinfunction "LED15_22") (pintype "passive"))
    )
    (net (code "64") (name "unconnected-(IC3-LED8-Pad15)") (class "Default")
      (node (ref "IC3") (pin "15") (pinfunction "LED8_15") (pintype "passive"))
    )
    (net (code "65") (name "unconnected-(IC3-LED9-Pad16)") (class "Default")
      (node (ref "IC3") (pin "16") (pinfunction "LED9_16") (pintype "passive"))
    )
    (net (code "66") (name "unconnected-(IC3-LED10-Pad17)") (class "Default")
      (node (ref "IC3") (pin "17") (pinfunction "LED10_17") (pintype "passive"))
    )
    (net (code "67") (name "unconnected-(IC3-LED11-Pad18)") (class "Default")
      (node (ref "IC3") (pin "18") (pinfunction "LED11_18") (pintype "passive"))
    )
    (net (code "68") (name "unconnected-(IC3-LED12-Pad19)") (class "Default")
      (node (ref "IC3") (pin "19") (pinfunction "LED12_19") (pintype "passive"))
    )
    (net (code "69") (name "unconnected-(IC3-LED13-Pad20)") (class "Default")
      (node (ref "IC3") (pin "20") (pinfunction "LED13_20") (pintype "passive"))
    )
    (net (code "70") (name "unconnected-(IC3-LED14-Pad21)") (class "Default")
      (node (ref "IC3") (pin "21") (pinfunction "LED14_21") (pintype "passive"))
    )
    (net (code "71") (name "unconnected-(IC3-LED15-Pad22)") (class "Default")
      (node (ref "IC3") (pin "22") (pinfunction "LED15_22") (pintype "passive"))
    )
  )
)
